# 15.net
KiCad netlist of a schematic drawn in Altium Designer
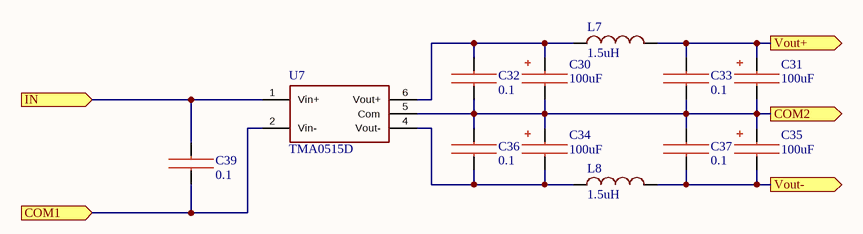
[diagram p0: 15.SchDoc]

(export (version "E")
  (design (tool "Eeschema 10.0.6"))
  (components
    (comp (ref "C30")
      (value "100uF")
      (footprint "TANTAL TYPE D")
      (libsource (lib "Capacitor") (part "Tantal D 100uF"))
    )
    (comp (ref "C31")
      (value "100uF")
      (footprint "TANTAL TYPE D")
      (libsource (lib "Capacitor") (part "Tantal D 100uF"))
    )
    (comp (ref "C32")
      (value "0.1")
      (footprint "Capacitor:CC0805_3D")
      (libsource (lib "Capacitor") (part "CC0805 X uF"))
    )
    (comp (ref "C33")
      (value "0.1")
      (footprint "Capacitor:CC0805_3D")
      (libsource (lib "Capacitor") (part "CC0805 X uF"))
    )
    (comp (ref "C34")
      (value "100uF")
      (footprint "TANTAL TYPE D")
      (libsource (lib "Capacitor") (part "Tantal D 100uF"))
    )
    (comp (ref "C35")
      (value "100uF")
      (footprint "TANTAL TYPE D")
      (libsource (lib "Capacitor") (part "Tantal D 100uF"))
    )
    (comp (ref "C36")
      (value "0.1")
      (footprint "Capacitor:CC0805_3D")
      (libsource (lib "Capacitor") (part "CC0805 X uF"))
    )
    (comp (ref "C37")
      (value "0.1")
      (footprint "Capacitor:CC0805_3D")
      (libsource (lib "Capacitor") (part "CC0805 X uF"))
    )
    (comp (ref "C39")
      (value "0.1")
      (footprint "Capacitor:CC0805_3D")
      (libsource (lib "Capacitor") (part "CC0805 X uF"))
    )
    (comp (ref "L7")
      (value "4700uH")
      (footprint "SDR0805:SDR0805")
      (libsource (lib "SDR0805") (part "SDR0805"))
    )
    (comp (ref "L8")
      (value "4700uH")
      (footprint "SDR0805:SDR0805")
      (libsource (lib "SDR0805") (part "SDR0805"))
    )
    (comp (ref "U7")
      (value "TMA0515D")
      (footprint "Dual")
      (description "5V to +/-15V TMA Series, 1 Watt")
      (libsource (lib "TMA") (part "TMA0515D"))
    )
  )
  (nets
    (net (code "1") (name "/COM1") (class "Default")
      (node (ref "C39") (pin "1") (pinfunction "1_1") (pintype "passive"))
      (node (ref "U7") (pin "2") (pinfunction "Vin-_2") (pintype "passive"))
    )
    (net (code "2") (name "/COM2") (class "Default")
      (node (ref "C30") (pin "1") (pinfunction "1_1") (pintype "passive"))
      (node (ref "C31") (pin "1") (pinfunction "1_1") (pintype "passive"))
      (node (ref "C32") (pin "1") (pinfunction "1_1") (pintype "passive"))
      (node (ref "C33") (pin "1") (pinfunction "1_1") (pintype "passive"))
      (node (ref "C34") (pin "2") (pinfunction "2_2") (pintype "passive"))
      (node (ref "C35") (pin "2") (pinfunction "2_2") (pintype "passive"))
      (node (ref "C36") (pin "2") (pinfunction "2_2") (pintype "passive"))
      (node (ref "C37") (pin "2") (pinfunction "2_2") (pintype "passive"))
      (node (ref "U7") (pin "5") (pinfunction "Com_5") (pintype "passive"))
    )
    (net (code "3") (name "/IN") (class "Default")
      (node (ref "C39") (pin "2") (pinfunction "2_2") (pintype "passive"))
      (node (ref "U7") (pin "1") (pinfunction "Vin+_1") (pintype "passive"))
    )
    (net (code "4") (name "/Vout+") (class "Default")
      (node (ref "C31") (pin "2") (pinfunction "2_2") (pintype "passive"))
      (node (ref "C33") (pin "2") (pinfunction "2_2") (pintype "passive"))
      (node (ref "L7") (pin "2") (pinfunction "2_2") (pintype "passive"))
    )
    (net (code "5") (name "/Vout-") (class "Default")
      (node (ref "C35") (pin "1") (pinfunction "1_1") (pintype "passive"))
      (node (ref "C37") (pin "1") (pinfunction "1_1") (pintype "passive"))
      (node (ref "L8") (pin "2") (pinfunction "2_2") (pintype "passive"))
    )
    (net (code "6") (name "Net-(U7-Vout+)") (class "Default")
      (node (ref "C30") (pin "2") (pinfunction "2_2") (pintype "passive"))
      (node (ref "C32") (pin "2") (pinfunction "2_2") (pintype "passive"))
      (node (ref "L7") (pin "1") (pinfunction "1_1") (pintype "passive"))
      (node (ref "U7") (pin "6") (pinfunction "Vout+_6") (pintype "passive"))
    )
    (net (code "7") (name "Net-(U7-Vout-)") (class "Default")
      (node (ref "C34") (pin "1") (pinfunction "1_1") (pintype "passive"))
      (node (ref "C36") (pin "1") (pinfunction "1_1") (pintype "passive"))
      (node (ref "L8") (pin "1") (pinfunction "1_1") (pintype "passive"))
      (node (ref "U7") (pin "4") (pinfunction "Vout-_4") (pintype "passive"))
    )
  )
)
